# Communication.net
KiCad netlist of a schematic drawn in Altium Designer
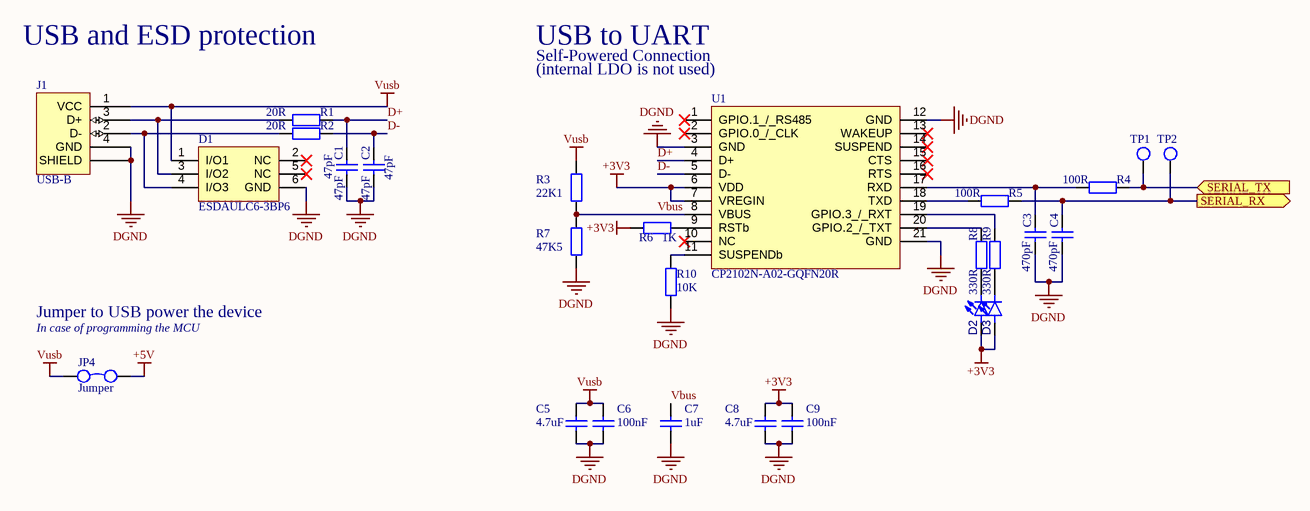
[diagram p0: Communication.SchDoc]

(export (version "E")
  (design (tool "Eeschema 10.0.6"))
  (components
    (comp (ref "C1")
      (value "47pF")
      (footprint "CAP0603")
      (fields
        (field (name "MANUFACTURER") "KEMET")
        (field (name "MANUFACTURER PART NUMBER") "C0603C470J1GACTU")
        (field (name "ALTIUM_VALUE") "47pF")
      )
      (libsource (lib "UPS_Schlib") (part "47pF"))
    )
    (comp (ref "C2")
      (value "47pF")
      (footprint "CAP0603")
      (fields
        (field (name "MANUFACTURER") "KEMET")
        (field (name "MANUFACTURER PART NUMBER") "C0603C470J1GACTU")
        (field (name "ALTIUM_VALUE") "47pF")
      )
      (libsource (lib "UPS_Schlib") (part "47pF"))
    )
    (comp (ref "C3")
      (value "470pF")
      (footprint "CAP0603")
      (fields
        (field (name "MANUFACTURER") "KEMET")
        (field (name "MANUFACTURER PART NUMBER") "C0603C471JAGACAUTO")
      )
      (libsource (lib "UPS_Schlib") (part "470pF"))
    )
    (comp (ref "C4")
      (value "470pF")
      (footprint "CAP0603")
      (fields
        (field (name "MANUFACTURER") "KEMET")
        (field (name "MANUFACTURER PART NUMBER") "C0603C471JAGACAUTO")
      )
      (libsource (lib "UPS_Schlib") (part "470pF"))
    )
    (comp (ref "C5")
      (value "4.7uF")
      (footprint "CAP0603")
      (description "Capacitor Ceramic 4.7uF 10V X5R 10% 0603 T/R")
      (fields
        (field (name "MANUFACTURER") "Samsung")
        (field (name "MANUFACTURER PART NUMBER") "CL10A475KP8NNWC")
      )
      (libsource (lib "UPS_Schlib") (part "4.7uF"))
    )
    (comp (ref "C6")
      (value "100nF")
      (footprint "CAP0603")
      (fields
        (field (name "MANUFACTURER") "Samsung")
        (field (name "MANUFACTURER PART NUMBER") "CL10B104KA8WPNC")
      )
      (libsource (lib "UPS_Schlib") (part "100nF"))
    )
    (comp (ref "C7")
      (value "1uF")
      (footprint "CAP0603")
      (fields
        (field (name "MANUFACTURER") "Walsin Technologies")
        (field (name "MANUFACTURER PART NUMBER") "SH18B105K160CT")
      )
      (libsource (lib "UPS_Schlib") (part "1uF"))
    )
    (comp (ref "C8")
      (value "4.7uF")
      (footprint "CAP0603")
      (description "Capacitor Ceramic 4.7uF 10V X5R 10% 0603 T/R")
      (fields
        (field (name "MANUFACTURER") "Samsung")
        (field (name "MANUFACTURER PART NUMBER") "CL10A475KP8NNWC")
      )
      (libsource (lib "UPS_Schlib") (part "4.7uF"))
    )
    (comp (ref "C9")
      (value "100nF")
      (footprint "CAP0603")
      (fields
        (field (name "MANUFACTURER") "Samsung")
        (field (name "MANUFACTURER PART NUMBER") "CL10B104KA8WPNC")
      )
      (libsource (lib "UPS_Schlib") (part "100nF"))
    )
    (comp (ref "D1")
      (value "ESDAULC6-3BP6")
      (footprint "SOT-666")
      (description "Trans Voltage Suppressor Diode, Bidirectional, 4 Element, Silicon")
      (fields
        (field (name "MOUSER PART NUMBER") "511-ESDAULC63BP6")
        (field (name "MANUFACTURER") "STMicroelectronics")
      )
      (libsource (lib "UPS_Schlib") (part "ESDAULC6-3BP6"))
    )
    (comp (ref "D2")
      (value "~")
      (footprint "LED0603")
      (description "Single Color LED, Bright Green, Water Clear, 1.1mm")
      (fields
        (field (name "MANUFACTURER") "Wurth Electronics")
        (field (name "MANUFACTURER PART NUMBER") "150060VS75000")
      )
      (libsource (lib "UPS_Schlib") (part "LED Green"))
    )
    (comp (ref "D3")
      (value "~")
      (footprint "LED0603")
      (description "Single Color LED, Bright Green, Water Clear, 1.1mm")
      (fields
        (field (name "MANUFACTURER") "Wurth Electronics")
        (field (name "MANUFACTURER PART NUMBER") "150060VS75000")
      )
      (libsource (lib "UPS_Schlib") (part "LED Green"))
    )
    (comp (ref "J1")
      (value "USB-B")
      (footprint "USB-B-FEMALE")
      (description "USB Connector, 4 Contact(s), Female, Right Angle, Solder Terminal, Receptacle")
      (fields
        (field (name "MANUFACTURER") "CUI Devices")
        (field (name "MANUFACTURER PART NUMBER") "UJ2-BH-W2-TH")
      )
      (libsource (lib "UPS_Schlib") (part "USB-B"))
    )
    (comp (ref "JP4")
      (value "Jumper")
      (footprint "PIN-1X2")
      (description "Interconnection Device")
      (fields (field (name "MANUFACTURER") "Harwin") (field (name "MANUFACTURER PART NUMBER") "M7582-46"))
      (libsource (lib "UPS_Schlib") (part "Jumper"))
    )
    (comp (ref "R1")
      (value "20R")
      (footprint "RES0603")
      (fields
        (field (name "MANUFACTURER") "Vishay")
        (field (name "MANUFACTURER PART NUMBER") "CRCW060320R0FKEA")
      )
      (libsource (lib "UPS_Schlib") (part "20R"))
    )
    (comp (ref "R2")
      (value "20R")
      (footprint "RES0603")
      (fields
        (field (name "MANUFACTURER") "Vishay")
        (field (name "MANUFACTURER PART NUMBER") "CRCW060320R0FKEA")
      )
      (libsource (lib "UPS_Schlib") (part "20R"))
    )
    (comp (ref "R3")
      (value "22K1")
      (footprint "RES0603")
      (description "22.1K F 1/16 0603")
      (fields
        (field (name "MANUFACTURER") "Mitsubishi Kamaya")
        (field (name "MANUFACTURER PART NUMBER") "RMC1/16K2212FTP")
      )
      (libsource (lib "UPS_Schlib") (part "22K1"))
    )
    (comp (ref "R4")
      (value "100R")
      (footprint "RES0603")
      (fields
        (field (name "MANUFACTURER") "Yageo")
        (field (name "MANUFACTURER PART NUMBER") "RC0603JR-13100RL")
      )
      (libsource (lib "UPS_Schlib") (part "100R"))
    )
    (comp (ref "R5")
      (value "100R")
      (footprint "RES0603")
      (fields
        (field (name "MANUFACTURER") "Yageo")
        (field (name "MANUFACTURER PART NUMBER") "RC0603JR-13100RL")
      )
      (libsource (lib "UPS_Schlib") (part "100R"))
    )
    (comp (ref "R6")
      (value "1K")
      (footprint "RES0603")
      (fields
        (field (name "MANUFACTURER") "Bourns")
        (field (name "MANUFACTURER PART NUMBER") "CR0603-FX-1001ELF")
      )
      (libsource (lib "UPS_Schlib") (part "1K"))
    )
    (comp (ref "R7")
      (value "47K5")
      (footprint "RES0603")
      (fields
        (field (name "MANUFACTURER") "Yageo")
        (field (name "MANUFACTURER PART NUMBER") "RC0603FR-0747K5L")
      )
      (libsource (lib "UPS_Schlib") (part "47K5"))
    )
    (comp (ref "R8")
      (value "330R")
      (footprint "RES0603")
      (fields
        (field (name "MANUFACTURER") "Walsin Technologies")
        (field (name "MANUFACTURER PART NUMBER") "WR06X3300FTL")
      )
      (libsource (lib "UPS_Schlib") (part "330R"))
    )
    (comp (ref "R9")
      (value "330R")
      (footprint "RES0603")
      (fields
        (field (name "MANUFACTURER") "Walsin Technologies")
        (field (name "MANUFACTURER PART NUMBER") "WR06X3300FTL")
      )
      (libsource (lib "UPS_Schlib") (part "330R"))
    )
    (comp (ref "R10")
      (value "10K")
      (footprint "RES0603")
      (fields
        (field (name "MANUFACTURER") "Bourns")
        (field (name "MANUFACTURER PART NUMBER") "CR0603-FX-1002ELF")
      )
      (libsource (lib "UPS_Schlib") (part "10K"))
    )
    (comp (ref "TP1")
      (value "Test Point")
      (footprint "TP-1.5HOLE")
      (libsource (lib "UPS_Schlib") (part "Test Point"))
    )
    (comp (ref "TP2")
      (value "Test Point")
      (footprint "TP-1.5HOLE")
      (libsource (lib "UPS_Schlib") (part "Test Point"))
    )
    (comp (ref "U1")
      (value "CP2102N-A02-GQFN20R")
      (footprint "QFN-20")
      (description "USB Bus Controller, CMOS")
      (fields
        (field (name "MOUSER PART NUMBER") "634-CP2102NA02QFN20R")
        (field (name "MANUFACTURER") "Silicon Labs")
      )
      (libsource (lib "UPS_Schlib") (part "CP2102N-A02-GQFN20R"))
    )
  )
  (nets
    (net (code "1") (name "+3V3") (class "Default")
      (node (ref "C8") (pin "2") (pinfunction "2_2") (pintype "passive"))
      (node (ref "C9") (pin "1") (pinfunction "1_1") (pintype "passive"))
      (node (ref "D2") (pin "2") (pinfunction "A_2") (pintype "passive"))
      (node (ref "D3") (pin "2") (pinfunction "A_2") (pintype "passive"))
      (node (ref "R6") (pin "1") (pinfunction "1_1") (pintype "passive"))
      (node (ref "U1") (pin "6") (pinfunction "VDD_6") (pintype "passive"))
      (node (ref "U1") (pin "7") (pinfunction "VREGIN_7") (pintype "passive"))
    )
    (net (code "2") (name "+5V") (class "Default") (node (ref "JP4") (pin "2") (pintype "passive")))
    (net (code "3") (name "/D+") (class "Default")
      (node (ref "C1") (pin "2") (pinfunction "2_2") (pintype "passive"))
      (node (ref "R1") (pin "1") (pinfunction "1_1") (pintype "passive"))
      (node (ref "U1") (pin "4") (pinfunction "D+_4") (pintype "passive"))
    )
    (net (code "4") (name "/D-") (class "Default")
      (node (ref "C2") (pin "2") (pinfunction "2_2") (pintype "passive"))
      (node (ref "R2") (pin "1") (pinfunction "1_1") (pintype "passive"))
      (node (ref "U1") (pin "5") (pinfunction "D-_5") (pintype "passive"))
    )
    (net (code "5") (name "/SERIAL_RX") (class "Default")
      (node (ref "C4") (pin "2") (pinfunction "2_2") (pintype "passive"))
      (node (ref "R5") (pin "2") (pinfunction "2_2") (pintype "passive"))
      (node (ref "TP2") (pin "1") (pintype "passive"))
    )
    (net (code "6") (name "/SERIAL_TX") (class "Default")
      (node (ref "R4") (pin "2") (pinfunction "2_2") (pintype "passive"))
      (node (ref "TP1") (pin "1") (pintype "passive"))
    )
    (net (code "7") (name "/Vbus") (class "Default")
      (node (ref "C7") (pin "2") (pinfunction "2_2") (pintype "passive"))
      (node (ref "R3") (pin "1") (pinfunction "1_1") (pintype "passive"))
      (node (ref "R7") (pin "2") (pinfunction "2_2") (pintype "passive"))
      (node (ref "U1") (pin "8") (pinfunction "VBUS_8") (pintype "passive"))
    )
    (net (code "8") (name "DGND") (class "Default")
      (node (ref "C1") (pin "1") (pinfunction "1_1") (pintype "passive"))
      (node (ref "C2") (pin "1") (pinfunction "1_1") (pintype "passive"))
      (node (ref "C3") (pin "1") (pinfunction "1_1") (pintype "passive"))
      (node (ref "C4") (pin "1") (pinfunction "1_1") (pintype "passive"))
      (node (ref "C5") (pin "1") (pinfunction "1_1") (pintype "passive"))
      (node (ref "C6") (pin "2") (pinfunction "2_2") (pintype "passive"))
      (node (ref "C7") (pin "1") (pinfunction "1_1") (pintype "passive"))
      (node (ref "C8") (pin "1") (pinfunction "1_1") (pintype "passive"))
      (node (ref "C9") (pin "2") (pinfunction "2_2") (pintype "passive"))
      (node (ref "D1") (pin "6") (pinfunction "GND_6") (pintype "passive"))
      (node (ref "J1") (pin "0") (pinfunction "SHIELD_0") (pintype "passive"))
      (node (ref "J1") (pin "4") (pinfunction "GND_4") (pintype "passive"))
      (node (ref "R10") (pin "1") (pinfunction "1_1") (pintype "passive"))
      (node (ref "R7") (pin "1") (pinfunction "1_1") (pintype "passive"))
      (node (ref "U1") (pin "12") (pinfunction "GND_12") (pintype "passive"))
      (node (ref "U1") (pin "21") (pinfunction "GND_21") (pintype "passive"))
      (node (ref "U1") (pin "3") (pinfunction "GND_3") (pintype "passive"))
    )
    (net (code "9") (name "Net-(D1-I{slash}O2)") (class "Default")
      (node (ref "D1") (pin "3") (pinfunction "I/O2_3") (pintype "passive"))
      (node (ref "J1") (pin "3") (pinfunction "D+_3") (pintype "bidirectional"))
      (node (ref "R1") (pin "2") (pinfunction "2_2") (pintype "passive"))
    )
    (net (code "10") (name "Net-(D1-I{slash}O3)") (class "Default")
      (node (ref "D1") (pin "4") (pinfunction "I/O3_4") (pintype "passive"))
      (node (ref "J1") (pin "2") (pinfunction "D-_2") (pintype "bidirectional"))
      (node (ref "R2") (pin "2") (pinfunction "2_2") (pintype "passive"))
    )
    (net (code "11") (name "Net-(D2-K)") (class "Default")
      (node (ref "D2") (pin "1") (pinfunction "K_1") (pintype "passive"))
      (node (ref "R8") (pin "2") (pinfunction "2_2") (pintype "passive"))
    )
    (net (code "12") (name "Net-(D3-K)") (class "Default")
      (node (ref "D3") (pin "1") (pinfunction "K_1") (pintype "passive"))
      (node (ref "R9") (pin "2") (pinfunction "2_2") (pintype "passive"))
    )
    (net (code "13") (name "Net-(U1-GPIO.2_{slash}_TXT)") (class "Default")
      (node (ref "R8") (pin "1") (pinfunction "1_1") (pintype "passive"))
      (node (ref "U1") (pin "20") (pinfunction "GPIO.2_/_TXT_20") (pintype "passive"))
    )
    (net (code "14") (name "Net-(U1-GPIO.3_{slash}_RXT)") (class "Default")
      (node (ref "R9") (pin "1") (pinfunction "1_1") (pintype "passive"))
      (node (ref "U1") (pin "19") (pinfunction "GPIO.3_/_RXT_19") (pintype "passive"))
    )
    (net (code "15") (name "Net-(U1-RSTb)") (class "Default")
      (node (ref "R6") (pin "2") (pinfunction "2_2") (pintype "passive"))
      (node (ref "U1") (pin "9") (pinfunction "RSTb_9") (pintype "passive"))
    )
    (net (code "16") (name "Net-(U1-RXD)") (class "Default")
      (node (ref "C3") (pin "2") (pinfunction "2_2") (pintype "passive"))
      (node (ref "R4") (pin "1") (pinfunction "1_1") (pintype "passive"))
      (node (ref "U1") (pin "17") (pinfunction "RXD_17") (pintype "passive"))
    )
    (net (code "17") (name "Net-(U1-SUSPENDb)") (class "Default")
      (node (ref "R10") (pin "2") (pinfunction "2_2") (pintype "passive"))
      (node (ref "U1") (pin "11") (pinfunction "SUSPENDb_11") (pintype "passive"))
    )
    (net (code "18") (name "Net-(U1-TXD)") (class "Default")
      (node (ref "R5") (pin "1") (pinfunction "1_1") (pintype "passive"))
      (node (ref "U1") (pin "18") (pinfunction "TXD_18") (pintype "passive"))
    )
    (net (code "19") (name "Vusb") (class "Default")
      (node (ref "C5") (pin "2") (pinfunction "2_2") (pintype "passive"))
      (node (ref "C6") (pin "1") (pinfunction "1_1") (pintype "passive"))
      (node (ref "D1") (pin "1") (pinfunction "I/O1_1") (pintype "passive"))
      (node (ref "J1") (pin "1") (pinfunction "VCC_1") (pintype "power_in"))
      (node (ref "JP4") (pin "1") (pintype "passive"))
      (node (ref "R3") (pin "2") (pinfunction "2_2") (pintype "passive"))
    )
    (net (code "20") (name "unconnected-(D1-NC-Pad2)") (class "Default")
      (node (ref "D1") (pin "2") (pinfunction "NC_2") (pintype "passive+no_connect"))
    )
    (net (code "21") (name "unconnected-(D1-NC-Pad5)") (class "Default")
      (node (ref "D1") (pin "5") (pinfunction "NC_5") (pintype "passive+no_connect"))
    )
    (net (code "22") (name "unconnected-(U1-CTS-Pad15)") (class "Default")
      (node (ref "U1") (pin "15") (pinfunction "CTS_15") (pintype "passive+no_connect"))
    )
    (net (code "23") (name "unconnected-(U1-GPIO.0_{slash}_CLK-Pad2)") (class "Default")
      (node (ref "U1") (pin "2") (pinfunction "GPIO.0_/_CLK_2") (pintype "passive+no_connect"))
    )
    (net (code "24") (name "unconnected-(U1-GPIO.1_{slash}_RS485-Pad1)") (class "Default")
      (node (ref "U1") (pin "1") (pinfunction "GPIO.1_/_RS485_1") (pintype "passive+no_connect"))
    )
    (net (code "25") (name "unconnected-(U1-NC-Pad10)") (class "Default")
      (node (ref "U1") (pin "10") (pinfunction "NC_10") (pintype "passive+no_connect"))
    )
    (net (code "26") (name "unconnected-(U1-RTS-Pad16)") (class "Default")
      (node (ref "U1") (pin "16") (pinfunction "RTS_16") (pintype "passive+no_connect"))
    )
    (net (code "27") (name "unconnected-(U1-SUSPEND-Pad14)") (class "Default")
      (node (ref "U1") (pin "14") (pinfunction "SUSPEND_14") (pintype "passive+no_connect"))
    )
    (net (code "28") (name "unconnected-(U1-WAKEUP-Pad13)") (class "Default")
      (node (ref "U1") (pin "13") (pinfunction "WAKEUP_13") (pintype "passive+no_connect"))
    )
  )
)
